# Zerow.net
KiCad netlist of a schematic drawn in EAGLE
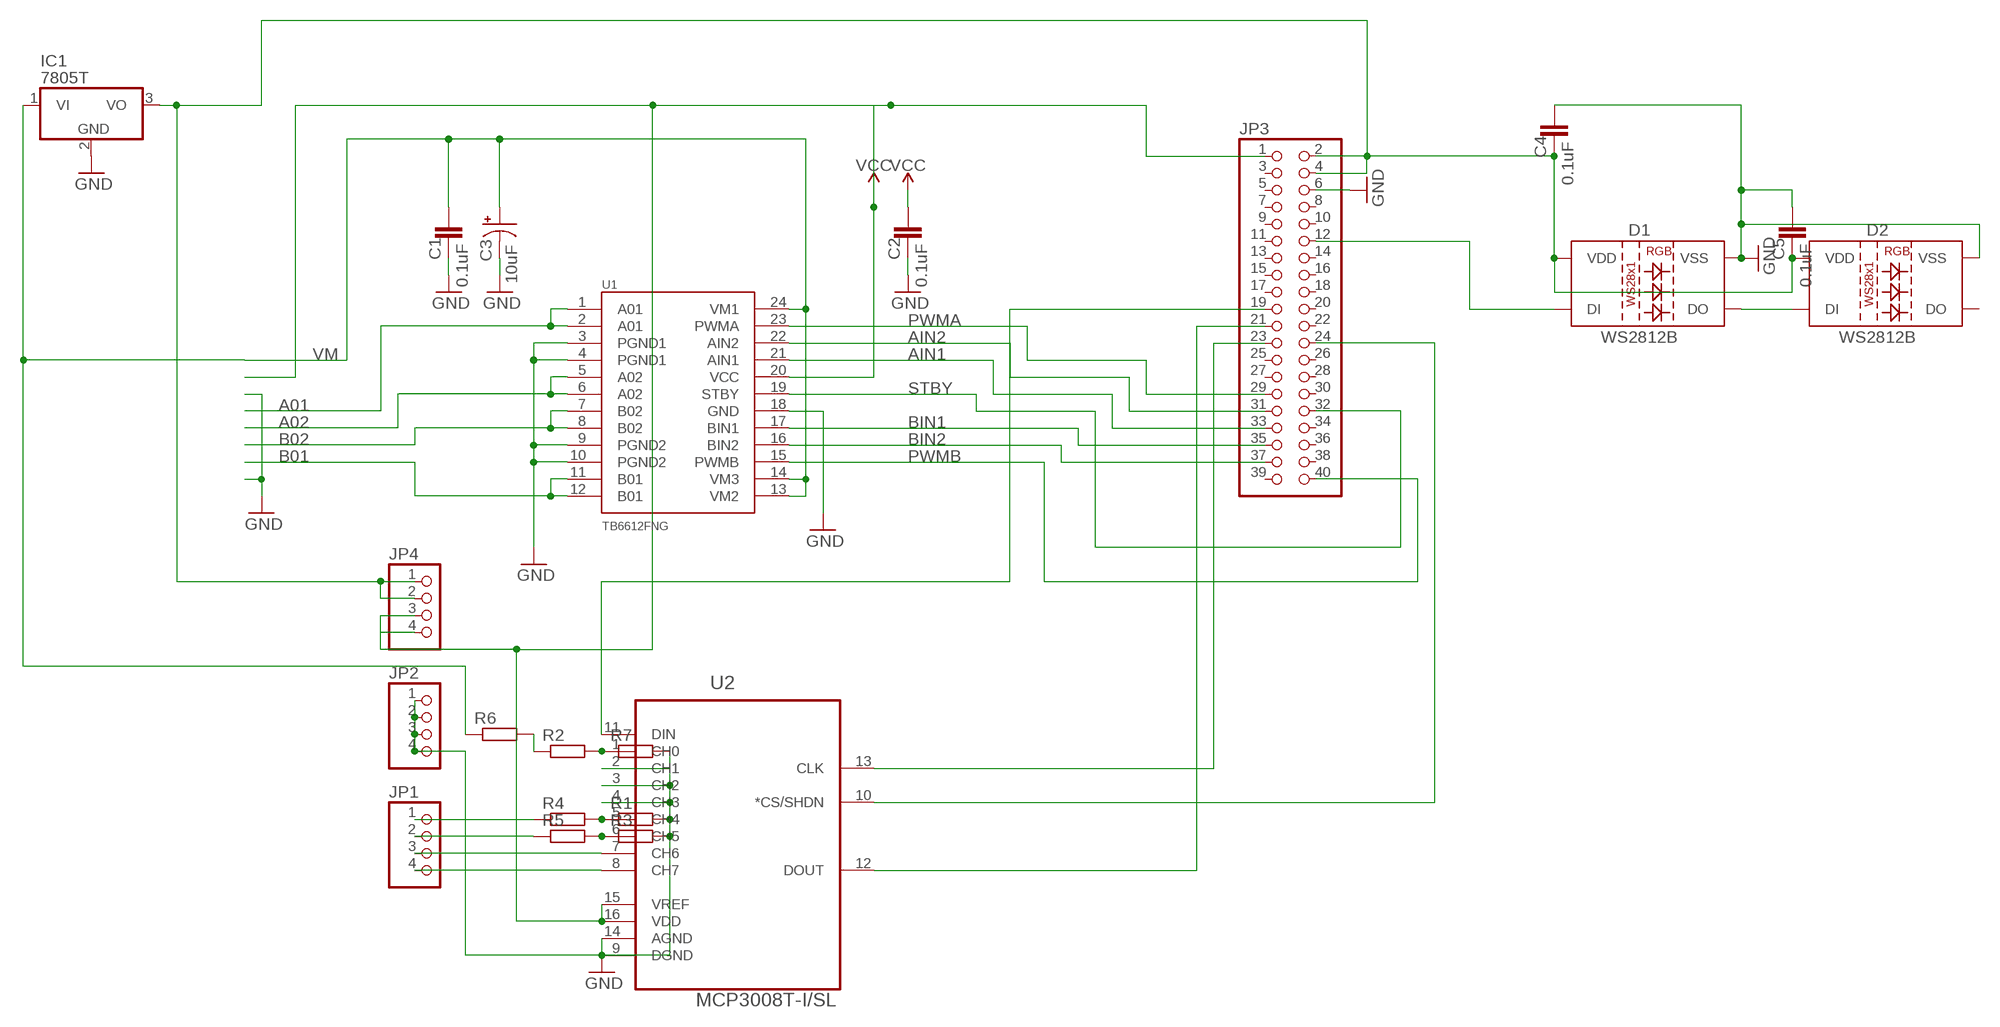
[diagram p0: schematic, sheet 2]

(export (version "E")
  (design (tool "Eeschema 10.0.6"))
  (components
    (comp (ref "C1")
      (value "0.1uF")
      (footprint "eagle-import:0402")
      (libsource (lib "eagle-import") (part "0.1UF-0402-16V-10%"))
    )
    (comp (ref "C2")
      (value "0.1uF")
      (footprint "eagle-import:0402")
      (libsource (lib "eagle-import") (part "0.1UF-0402-16V-10%"))
    )
    (comp (ref "C3")
      (value "10uF")
      (footprint "eagle-import:EIA3528")
      (libsource (lib "eagle-import") (part "10UF-POLAR-EIA3528-20V-10%(TANT)"))
    )
    (comp (ref "C4")
      (value "0.1uF")
      (footprint "eagle-import:0402")
      (libsource (lib "eagle-import") (part "0.1UF-0402-16V-10%"))
    )
    (comp (ref "C5")
      (value "0.1uF")
      (footprint "eagle-import:0402")
      (libsource (lib "eagle-import") (part "0.1UF-0402-16V-10%"))
    )
    (comp (ref "D1")
      (value "WS2812B")
      (footprint "eagle-import:WS2812B")
      (libsource (lib "eagle-import") (part "WS2812B"))
    )
    (comp (ref "D2")
      (value "WS2812B")
      (footprint "eagle-import:WS2812B")
      (libsource (lib "eagle-import") (part "WS2812B"))
    )
    (comp (ref "IC1")
      (value "7805T")
      (footprint "eagle-import:TO220H")
      (libsource (lib "eagle-import") (part "78T05"))
    )
    (comp (ref "JP1")
      (value "PINHD-1X4")
      (footprint "eagle-import:1X04")
      (libsource (lib "eagle-import") (part "PINHD-1X4"))
    )
    (comp (ref "JP2")
      (value "PINHD-1X4")
      (footprint "eagle-import:1X04")
      (libsource (lib "eagle-import") (part "PINHD-1X4"))
    )
    (comp (ref "JP3")
      (value "PINHD-2X20")
      (footprint "eagle-import:2X20")
      (libsource (lib "eagle-import") (part "PINHD-2X20"))
    )
    (comp (ref "JP4")
      (value "PINHD-1X4")
      (footprint "eagle-import:1X04")
      (libsource (lib "eagle-import") (part "PINHD-1X4"))
    )
    (comp (ref "R1")
      (value "R-EU_R0805")
      (footprint "eagle-import:R0805")
      (libsource (lib "eagle-import") (part "R-EU_R0805"))
    )
    (comp (ref "R2")
      (value "R-EU_R0805")
      (footprint "eagle-import:R0805")
      (libsource (lib "eagle-import") (part "R-EU_R0805"))
    )
    (comp (ref "R3")
      (value "R-EU_R0805")
      (footprint "eagle-import:R0805")
      (libsource (lib "eagle-import") (part "R-EU_R0805"))
    )
    (comp (ref "R4")
      (value "R-EU_R0805")
      (footprint "eagle-import:R0805")
      (libsource (lib "eagle-import") (part "R-EU_R0805"))
    )
    (comp (ref "R5")
      (value "R-EU_R0805")
      (footprint "eagle-import:R0805")
      (libsource (lib "eagle-import") (part "R-EU_R0805"))
    )
    (comp (ref "R6")
      (value "R-EU_R0805")
      (footprint "eagle-import:R0805")
      (libsource (lib "eagle-import") (part "R-EU_R0805"))
    )
    (comp (ref "R7")
      (value "R-EU_R0805")
      (footprint "eagle-import:R0805")
      (libsource (lib "eagle-import") (part "R-EU_R0805"))
    )
    (comp (ref "U1")
      (value "TB6612FNG")
      (footprint "eagle-import:SSOP24")
      (libsource (lib "eagle-import") (part "TB6612FNG"))
    )
    (comp (ref "U2")
      (value "MCP3008T-I/SL")
      (footprint "eagle-import:SOIC127P600X175-16N")
      (fields (field (name "DIGI-KEY_PART_NUMBER") "MCP3008T-I/SLCT-ND") (field (name "MF") "Microchip"))
      (libsource (lib "eagle-import") (part "MCP3008T-I/SL"))
    )
  )
  (nets
    (net (code "1") (name "A01") (class "Default")
      (node (ref "U1") (pin "1") (pinfunction "A01_1") (pintype "bidirectional"))
      (node (ref "U1") (pin "2") (pinfunction "A01_2") (pintype "bidirectional"))
    )
    (net (code "2") (name "A02") (class "Default")
      (node (ref "U1") (pin "5") (pinfunction "A02_5") (pintype "bidirectional"))
      (node (ref "U1") (pin "6") (pinfunction "A02_6") (pintype "bidirectional"))
    )
    (net (code "3") (name "AIN1") (class "Default")
      (node (ref "JP3") (pin "33") (pinfunction "33_33") (pintype "passive"))
      (node (ref "U1") (pin "21") (pinfunction "AIN1_21") (pintype "bidirectional"))
    )
    (net (code "4") (name "AIN2") (class "Default")
      (node (ref "JP3") (pin "31") (pinfunction "31_31") (pintype "passive"))
      (node (ref "U1") (pin "22") (pinfunction "AIN2_22") (pintype "bidirectional"))
    )
    (net (code "5") (name "B01") (class "Default")
      (node (ref "U1") (pin "11") (pinfunction "B01_11") (pintype "bidirectional"))
      (node (ref "U1") (pin "12") (pinfunction "B01_12") (pintype "bidirectional"))
    )
    (net (code "6") (name "B02") (class "Default")
      (node (ref "U1") (pin "7") (pinfunction "B02_7") (pintype "bidirectional"))
      (node (ref "U1") (pin "8") (pinfunction "B02_8") (pintype "bidirectional"))
    )
    (net (code "7") (name "BIN1") (class "Default")
      (node (ref "JP3") (pin "35") (pinfunction "35_35") (pintype "passive"))
      (node (ref "U1") (pin "17") (pinfunction "BIN1_17") (pintype "bidirectional"))
    )
    (net (code "8") (name "BIN2") (class "Default")
      (node (ref "JP3") (pin "37") (pinfunction "37_37") (pintype "passive"))
      (node (ref "U1") (pin "16") (pinfunction "BIN2_16") (pintype "bidirectional"))
    )
    (net (code "9") (name "GND") (class "Default")
      (node (ref "C1") (pin "2") (pinfunction "2_2") (pintype "passive"))
      (node (ref "C2") (pin "2") (pinfunction "2_2") (pintype "passive"))
      (node (ref "C3") (pin "C") (pinfunction "-_C") (pintype "passive"))
      (node (ref "C4") (pin "1") (pinfunction "1_1") (pintype "passive"))
      (node (ref "C5") (pin "1") (pinfunction "1_1") (pintype "passive"))
      (node (ref "D1") (pin "3") (pinfunction "VSS_3") (pintype "bidirectional"))
      (node (ref "D2") (pin "3") (pinfunction "VSS_3") (pintype "bidirectional"))
      (node (ref "IC1") (pin "2") (pinfunction "GND_2") (pintype "passive"))
      (node (ref "JP2") (pin "1") (pinfunction "1_1") (pintype "passive"))
      (node (ref "JP2") (pin "2") (pinfunction "2_2") (pintype "passive"))
      (node (ref "JP2") (pin "3") (pinfunction "3_3") (pintype "passive"))
      (node (ref "JP2") (pin "4") (pinfunction "4_4") (pintype "passive"))
      (node (ref "JP3") (pin "6") (pinfunction "6_6") (pintype "passive"))
      (node (ref "R1") (pin "2") (pinfunction "2_2") (pintype "passive"))
      (node (ref "R3") (pin "2") (pinfunction "2_2") (pintype "passive"))
      (node (ref "R7") (pin "2") (pinfunction "2_2") (pintype "passive"))
      (node (ref "U1") (pin "10") (pinfunction "PGND2_10") (pintype "bidirectional"))
      (node (ref "U1") (pin "18") (pinfunction "GND_18") (pintype "bidirectional"))
      (node (ref "U1") (pin "3") (pinfunction "PGND1_3") (pintype "bidirectional"))
      (node (ref "U1") (pin "4") (pinfunction "PGND1_4") (pintype "bidirectional"))
      (node (ref "U1") (pin "9") (pinfunction "PGND2_9") (pintype "bidirectional"))
      (node (ref "U2") (pin "14") (pinfunction "AGND_14") (pintype "passive"))
      (node (ref "U2") (pin "2") (pinfunction "CH1_2") (pintype "input"))
      (node (ref "U2") (pin "3") (pinfunction "CH2_3") (pintype "input"))
      (node (ref "U2") (pin "4") (pinfunction "CH3_4") (pintype "input"))
      (node (ref "U2") (pin "9") (pinfunction "DGND_9") (pintype "passive"))
    )
    (net (code "10") (name "Net-(D1-DI)") (class "Default")
      (node (ref "D1") (pin "4") (pinfunction "DI_4") (pintype "bidirectional"))
      (node (ref "JP3") (pin "12") (pinfunction "12_12") (pintype "passive"))
    )
    (net (code "11") (name "Net-(D1-DO)") (class "Default")
      (node (ref "D1") (pin "2") (pinfunction "DO_2") (pintype "bidirectional"))
      (node (ref "D2") (pin "4") (pinfunction "DI_4") (pintype "bidirectional"))
    )
    (net (code "12") (name "Net-(D1-VDD)") (class "Default")
      (node (ref "C4") (pin "2") (pinfunction "2_2") (pintype "passive"))
      (node (ref "C5") (pin "2") (pinfunction "2_2") (pintype "passive"))
      (node (ref "D1") (pin "1") (pinfunction "VDD_1") (pintype "bidirectional"))
      (node (ref "D2") (pin "1") (pinfunction "VDD_1") (pintype "bidirectional"))
      (node (ref "IC1") (pin "3") (pinfunction "VO_3") (pintype "passive"))
      (node (ref "JP3") (pin "2") (pinfunction "2_2") (pintype "passive"))
      (node (ref "JP3") (pin "4") (pinfunction "4_4") (pintype "passive"))
      (node (ref "JP4") (pin "1") (pinfunction "1_1") (pintype "passive"))
      (node (ref "JP4") (pin "2") (pinfunction "2_2") (pintype "passive"))
    )
    (net (code "13") (name "Net-(JP1-Pad1)") (class "Default")
      (node (ref "JP1") (pin "1") (pinfunction "1_1") (pintype "passive"))
      (node (ref "R4") (pin "1") (pinfunction "1_1") (pintype "passive"))
    )
    (net (code "14") (name "Net-(JP1-Pad2)") (class "Default")
      (node (ref "JP1") (pin "2") (pinfunction "2_2") (pintype "passive"))
      (node (ref "R5") (pin "1") (pinfunction "1_1") (pintype "passive"))
    )
    (net (code "15") (name "Net-(R2-Pad1)") (class "Default")
      (node (ref "R2") (pin "1") (pinfunction "1_1") (pintype "passive"))
      (node (ref "R6") (pin "2") (pinfunction "2_2") (pintype "passive"))
    )
    (net (code "16") (name "Net-(U2-*CS{slash}SHDN)") (class "Default")
      (node (ref "JP3") (pin "24") (pinfunction "24_24") (pintype "passive"))
      (node (ref "U2") (pin "10") (pinfunction "*CS/SHDN_10") (pintype "input"))
    )
    (net (code "17") (name "Net-(U2-CH0)") (class "Default")
      (node (ref "R2") (pin "2") (pinfunction "2_2") (pintype "passive"))
      (node (ref "R7") (pin "1") (pinfunction "1_1") (pintype "passive"))
      (node (ref "U2") (pin "1") (pinfunction "CH0_1") (pintype "input"))
    )
    (net (code "18") (name "Net-(U2-CH4)") (class "Default")
      (node (ref "R1") (pin "1") (pinfunction "1_1") (pintype "passive"))
      (node (ref "R4") (pin "2") (pinfunction "2_2") (pintype "passive"))
      (node (ref "U2") (pin "5") (pinfunction "CH4_5") (pintype "input"))
    )
    (net (code "19") (name "Net-(U2-CH5)") (class "Default")
      (node (ref "R3") (pin "1") (pinfunction "1_1") (pintype "passive"))
      (node (ref "R5") (pin "2") (pinfunction "2_2") (pintype "passive"))
      (node (ref "U2") (pin "6") (pinfunction "CH5_6") (pintype "input"))
    )
    (net (code "20") (name "Net-(U2-CH6)") (class "Default")
      (node (ref "JP1") (pin "3") (pinfunction "3_3") (pintype "passive"))
      (node (ref "U2") (pin "7") (pinfunction "CH6_7") (pintype "input"))
    )
    (net (code "21") (name "Net-(U2-CH7)") (class "Default")
      (node (ref "JP1") (pin "4") (pinfunction "4_4") (pintype "passive"))
      (node (ref "U2") (pin "8") (pinfunction "CH7_8") (pintype "input"))
    )
    (net (code "22") (name "Net-(U2-CLK)") (class "Default")
      (node (ref "JP3") (pin "23") (pinfunction "23_23") (pintype "passive"))
      (node (ref "U2") (pin "13") (pinfunction "CLK_13") (pintype "input"))
    )
    (net (code "23") (name "Net-(U2-DIN)") (class "Default")
      (node (ref "JP3") (pin "19") (pinfunction "19_19") (pintype "passive"))
      (node (ref "U2") (pin "11") (pinfunction "DIN_11") (pintype "input"))
    )
    (net (code "24") (name "Net-(U2-DOUT)") (class "Default")
      (node (ref "JP3") (pin "21") (pinfunction "21_21") (pintype "passive"))
      (node (ref "U2") (pin "12") (pinfunction "DOUT_12") (pintype "output"))
    )
    (net (code "25") (name "PWMA") (class "Default")
      (node (ref "JP3") (pin "29") (pinfunction "29_29") (pintype "passive"))
      (node (ref "U1") (pin "23") (pinfunction "PWMA_23") (pintype "bidirectional"))
    )
    (net (code "26") (name "PWMB") (class "Default")
      (node (ref "JP3") (pin "40") (pinfunction "40_40") (pintype "passive"))
      (node (ref "U1") (pin "15") (pinfunction "PWMB_15") (pintype "bidirectional"))
    )
    (net (code "27") (name "STBY") (class "Default")
      (node (ref "JP3") (pin "32") (pinfunction "32_32") (pintype "passive"))
      (node (ref "U1") (pin "19") (pinfunction "STBY_19") (pintype "bidirectional"))
    )
    (net (code "28") (name "VCC") (class "Default")
      (node (ref "C2") (pin "1") (pinfunction "1_1") (pintype "passive"))
      (node (ref "JP3") (pin "1") (pinfunction "1_1") (pintype "passive"))
      (node (ref "JP4") (pin "3") (pinfunction "3_3") (pintype "passive"))
      (node (ref "JP4") (pin "4") (pinfunction "4_4") (pintype "passive"))
      (node (ref "U1") (pin "20") (pinfunction "VCC_20") (pintype "bidirectional"))
      (node (ref "U2") (pin "15") (pinfunction "VREF_15") (pintype "input"))
      (node (ref "U2") (pin "16") (pinfunction "VDD_16") (pintype "power_in"))
    )
    (net (code "29") (name "VM") (class "Default")
      (node (ref "C1") (pin "1") (pinfunction "1_1") (pintype "passive"))
      (node (ref "C3") (pin "A") (pinfunction "+_A") (pintype "passive"))
      (node (ref "IC1") (pin "1") (pinfunction "VI_1") (pintype "input"))
      (node (ref "R6") (pin "1") (pinfunction "1_1") (pintype "passive"))
      (node (ref "U1") (pin "13") (pinfunction "VM2_13") (pintype "bidirectional"))
      (node (ref "U1") (pin "14") (pinfunction "VM3_14") (pintype "bidirectional"))
      (node (ref "U1") (pin "24") (pinfunction "VM1_24") (pintype "bidirectional"))
    )
    (net (code "30") (name "unconnected-(D2-DO-Pad2)") (class "Default")
      (node (ref "D2") (pin "2") (pinfunction "DO_2") (pintype "bidirectional"))
    )
    (net (code "31") (name "unconnected-(JP3-Pad3)") (class "Default")
      (node (ref "JP3") (pin "3") (pinfunction "3_3") (pintype "passive"))
    )
    (net (code "32") (name "unconnected-(JP3-Pad5)") (class "Default")
      (node (ref "JP3") (pin "5") (pinfunction "5_5") (pintype "passive"))
    )
    (net (code "33") (name "unconnected-(JP3-Pad7)") (class "Default")
      (node (ref "JP3") (pin "7") (pinfunction "7_7") (pintype "passive"))
    )
    (net (code "34") (name "unconnected-(JP3-Pad8)") (class "Default")
      (node (ref "JP3") (pin "8") (pinfunction "8_8") (pintype "passive"))
    )
    (net (code "35") (name "unconnected-(JP3-Pad9)") (class "Default")
      (node (ref "JP3") (pin "9") (pinfunction "9_9") (pintype "passive"))
    )
    (net (code "36") (name "unconnected-(JP3-Pad10)") (class "Default")
      (node (ref "JP3") (pin "10") (pinfunction "10_10") (pintype "passive"))
    )
    (net (code "37") (name "unconnected-(JP3-Pad11)") (class "Default")
      (node (ref "JP3") (pin "11") (pinfunction "11_11") (pintype "passive"))
    )
    (net (code "38") (name "unconnected-(JP3-Pad13)") (class "Default")
      (node (ref "JP3") (pin "13") (pinfunction "13_13") (pintype "passive"))
    )
    (net (code "39") (name "unconnected-(JP3-Pad14)") (class "Default")
      (node (ref "JP3") (pin "14") (pinfunction "14_14") (pintype "passive"))
    )
    (net (code "40") (name "unconnected-(JP3-Pad15)") (class "Default")
      (node (ref "JP3") (pin "15") (pinfunction "15_15") (pintype "passive"))
    )
    (net (code "41") (name "unconnected-(JP3-Pad16)") (class "Default")
      (node (ref "JP3") (pin "16") (pinfunction "16_16") (pintype "passive"))
    )
    (net (code "42") (name "unconnected-(JP3-Pad17)") (class "Default")
      (node (ref "JP3") (pin "17") (pinfunction "17_17") (pintype "passive"))
    )
    (net (code "43") (name "unconnected-(JP3-Pad18)") (class "Default")
      (node (ref "JP3") (pin "18") (pinfunction "18_18") (pintype "passive"))
    )
    (net (code "44") (name "unconnected-(JP3-Pad20)") (class "Default")
      (node (ref "JP3") (pin "20") (pinfunction "20_20") (pintype "passive"))
    )
    (net (code "45") (name "unconnected-(JP3-Pad22)") (class "Default")
      (node (ref "JP3") (pin "22") (pinfunction "22_22") (pintype "passive"))
    )
    (net (code "46") (name "unconnected-(JP3-Pad25)") (class "Default")
      (node (ref "JP3") (pin "25") (pinfunction "25_25") (pintype "passive"))
    )
    (net (code "47") (name "unconnected-(JP3-Pad26)") (class "Default")
      (node (ref "JP3") (pin "26") (pinfunction "26_26") (pintype "passive"))
    )
    (net (code "48") (name "unconnected-(JP3-Pad27)") (class "Default")
      (node (ref "JP3") (pin "27") (pinfunction "27_27") (pintype "passive"))
    )
    (net (code "49") (name "unconnected-(JP3-Pad28)") (class "Default")
      (node (ref "JP3") (pin "28") (pinfunction "28_28") (pintype "passive"))
    )
    (net (code "50") (name "unconnected-(JP3-Pad30)") (class "Default")
      (node (ref "JP3") (pin "30") (pinfunction "30_30") (pintype "passive"))
    )
    (net (code "51") (name "unconnected-(JP3-Pad34)") (class "Default")
      (node (ref "JP3") (pin "34") (pinfunction "34_34") (pintype "passive"))
    )
    (net (code "52") (name "unconnected-(JP3-Pad36)") (class "Default")
      (node (ref "JP3") (pin "36") (pinfunction "36_36") (pintype "passive"))
    )
    (net (code "53") (name "unconnected-(JP3-Pad38)") (class "Default")
      (node (ref "JP3") (pin "38") (pinfunction "38_38") (pintype "passive"))
    )
    (net (code "54") (name "unconnected-(JP3-Pad39)") (class "Default")
      (node (ref "JP3") (pin "39") (pinfunction "39_39") (pintype "passive"))
    )
  )
)
